# Conn4_3.net
KiCad netlist of a schematic drawn in Altium Designer
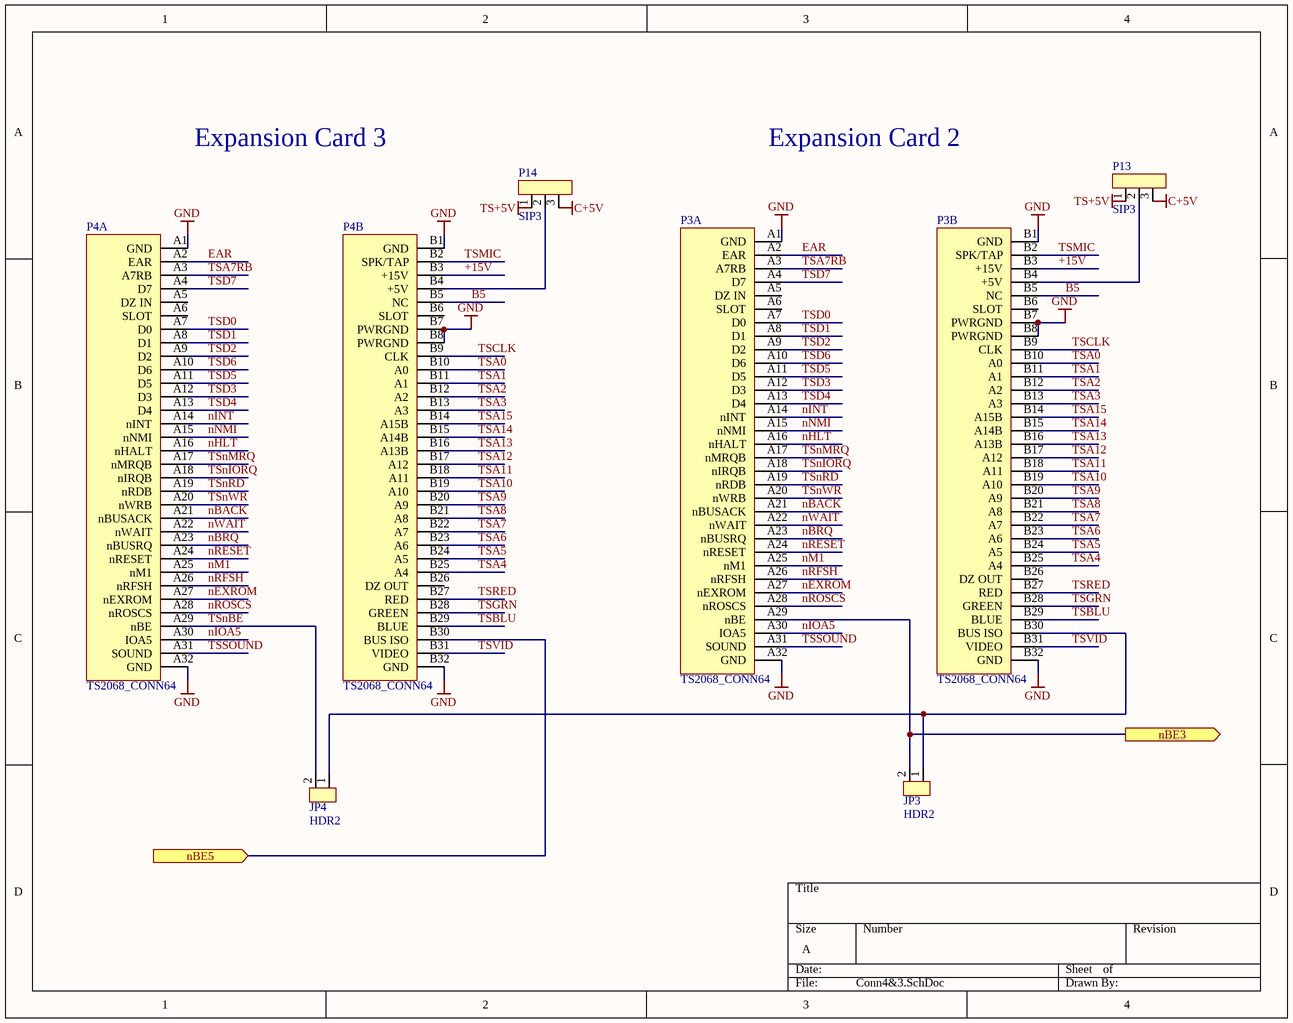
[diagram p0: Conn4&3.SchDoc]

(export (version "E")
  (design (tool "Eeschema 10.0.6"))
  (components
    (comp (ref "JP3") (value "HDR2") (footprint "HDR2") (libsource (lib "Connectors") (part "HDR2")))
    (comp (ref "JP4") (value "HDR2") (footprint "HDR2") (libsource (lib "Connectors") (part "HDR2")))
    (comp (ref "P3")
      (value "TS2068_CONN64")
      (footprint "64CARDEDGE")
      (description "64 Position Female Connector Non Specified - Dual Edge Gold 0.100\" (2.54mm) Black")
      (fields (field (name "MFG") "TD"))
      (libsource (lib "Connectors") (part "TS2068_CONN64"))
    )
    (comp (ref "P4")
      (value "TS2068_CONN64")
      (footprint "64CARDEDGE")
      (description "64 Position Female Connector Non Specified - Dual Edge Gold 0.100\" (2.54mm) Black")
      (fields (field (name "MFG") "TD"))
      (libsource (lib "Connectors") (part "TS2068_CONN64"))
    )
    (comp (ref "P13") (value "SIP3") (footprint "SIP3") (libsource (lib "Connectors") (part "SIP3")))
    (comp (ref "P14") (value "SIP3") (footprint "SIP3") (libsource (lib "Connectors") (part "SIP3")))
  )
  (nets
    (net (code "1") (name "/+15V") (class "Default")
      (node (ref "P3") (pin "B3") (pinfunction "+15V_B3") (pintype "passive"))
      (node (ref "P4") (pin "B3") (pinfunction "+15V_B3") (pintype "passive"))
    )
    (net (code "2") (name "/B5") (class "Default")
      (node (ref "P3") (pin "B5") (pinfunction "NC_B5") (pintype "passive"))
      (node (ref "P4") (pin "B5") (pinfunction "NC_B5") (pintype "passive"))
    )
    (net (code "3") (name "/EAR") (class "Default")
      (node (ref "P3") (pin "A2") (pinfunction "EAR_A2") (pintype "passive"))
      (node (ref "P4") (pin "A2") (pinfunction "EAR_A2") (pintype "passive"))
    )
    (net (code "4") (name "/TSA0") (class "Default")
      (node (ref "P3") (pin "B10") (pinfunction "A0_B10") (pintype "passive"))
      (node (ref "P4") (pin "B10") (pinfunction "A0_B10") (pintype "passive"))
    )
    (net (code "5") (name "/TSA1") (class "Default")
      (node (ref "P3") (pin "B11") (pinfunction "A1_B11") (pintype "passive"))
      (node (ref "P4") (pin "B11") (pinfunction "A1_B11") (pintype "passive"))
    )
    (net (code "6") (name "/TSA2") (class "Default")
      (node (ref "P3") (pin "B12") (pinfunction "A2_B12") (pintype "passive"))
      (node (ref "P4") (pin "B12") (pinfunction "A2_B12") (pintype "passive"))
    )
    (net (code "7") (name "/TSA3") (class "Default")
      (node (ref "P3") (pin "B13") (pinfunction "A3_B13") (pintype "passive"))
      (node (ref "P4") (pin "B13") (pinfunction "A3_B13") (pintype "passive"))
    )
    (net (code "8") (name "/TSA4") (class "Default")
      (node (ref "P3") (pin "B25") (pinfunction "A4_B25") (pintype "passive"))
      (node (ref "P4") (pin "B25") (pinfunction "A4_B25") (pintype "passive"))
    )
    (net (code "9") (name "/TSA5") (class "Default")
      (node (ref "P3") (pin "B24") (pinfunction "A5_B24") (pintype "passive"))
      (node (ref "P4") (pin "B24") (pinfunction "A5_B24") (pintype "passive"))
    )
    (net (code "10") (name "/TSA6") (class "Default")
      (node (ref "P3") (pin "B23") (pinfunction "A6_B23") (pintype "passive"))
      (node (ref "P4") (pin "B23") (pinfunction "A6_B23") (pintype "passive"))
    )
    (net (code "11") (name "/TSA7") (class "Default")
      (node (ref "P3") (pin "B22") (pinfunction "A7_B22") (pintype "passive"))
      (node (ref "P4") (pin "B22") (pinfunction "A7_B22") (pintype "passive"))
    )
    (net (code "12") (name "/TSA7RB") (class "Default")
      (node (ref "P3") (pin "A3") (pinfunction "A7RB_A3") (pintype "passive"))
      (node (ref "P4") (pin "A3") (pinfunction "A7RB_A3") (pintype "passive"))
    )
    (net (code "13") (name "/TSA8") (class "Default")
      (node (ref "P3") (pin "B21") (pinfunction "A8_B21") (pintype "passive"))
      (node (ref "P4") (pin "B21") (pinfunction "A8_B21") (pintype "passive"))
    )
    (net (code "14") (name "/TSA9") (class "Default")
      (node (ref "P3") (pin "B20") (pinfunction "A9_B20") (pintype "passive"))
      (node (ref "P4") (pin "B20") (pinfunction "A9_B20") (pintype "passive"))
    )
    (net (code "15") (name "/TSA10") (class "Default")
      (node (ref "P3") (pin "B19") (pinfunction "A10_B19") (pintype "passive"))
      (node (ref "P4") (pin "B19") (pinfunction "A10_B19") (pintype "passive"))
    )
    (net (code "16") (name "/TSA11") (class "Default")
      (node (ref "P3") (pin "B18") (pinfunction "A11_B18") (pintype "passive"))
      (node (ref "P4") (pin "B18") (pinfunction "A11_B18") (pintype "passive"))
    )
    (net (code "17") (name "/TSA12") (class "Default")
      (node (ref "P3") (pin "B17") (pinfunction "A12_B17") (pintype "passive"))
      (node (ref "P4") (pin "B17") (pinfunction "A12_B17") (pintype "passive"))
    )
    (net (code "18") (name "/TSA13") (class "Default")
      (node (ref "P3") (pin "B16") (pinfunction "A13B_B16") (pintype "passive"))
      (node (ref "P4") (pin "B16") (pinfunction "A13B_B16") (pintype "passive"))
    )
    (net (code "19") (name "/TSA14") (class "Default")
      (node (ref "P3") (pin "B15") (pinfunction "A14B_B15") (pintype "passive"))
      (node (ref "P4") (pin "B15") (pinfunction "A14B_B15") (pintype "passive"))
    )
    (net (code "20") (name "/TSA15") (class "Default")
      (node (ref "P3") (pin "B14") (pinfunction "A15B_B14") (pintype "passive"))
      (node (ref "P4") (pin "B14") (pinfunction "A15B_B14") (pintype "passive"))
    )
    (net (code "21") (name "/TSBLU") (class "Default")
      (node (ref "P3") (pin "B29") (pinfunction "BLUE_B29") (pintype "passive"))
      (node (ref "P4") (pin "B29") (pinfunction "BLUE_B29") (pintype "passive"))
    )
    (net (code "22") (name "/TSCLK") (class "Default")
      (node (ref "P3") (pin "B9") (pinfunction "CLK_B9") (pintype "passive"))
      (node (ref "P4") (pin "B9") (pinfunction "CLK_B9") (pintype "passive"))
    )
    (net (code "23") (name "/TSD0") (class "Default")
      (node (ref "P3") (pin "A7") (pinfunction "D0_A7") (pintype "passive"))
      (node (ref "P4") (pin "A7") (pinfunction "D0_A7") (pintype "passive"))
    )
    (net (code "24") (name "/TSD1") (class "Default")
      (node (ref "P3") (pin "A8") (pinfunction "D1_A8") (pintype "passive"))
      (node (ref "P4") (pin "A8") (pinfunction "D1_A8") (pintype "passive"))
    )
    (net (code "25") (name "/TSD2") (class "Default")
      (node (ref "P3") (pin "A9") (pinfunction "D2_A9") (pintype "passive"))
      (node (ref "P4") (pin "A9") (pinfunction "D2_A9") (pintype "passive"))
    )
    (net (code "26") (name "/TSD3") (class "Default")
      (node (ref "P3") (pin "A12") (pinfunction "D3_A12") (pintype "passive"))
      (node (ref "P4") (pin "A12") (pinfunction "D3_A12") (pintype "passive"))
    )
    (net (code "27") (name "/TSD4") (class "Default")
      (node (ref "P3") (pin "A13") (pinfunction "D4_A13") (pintype "passive"))
      (node (ref "P4") (pin "A13") (pinfunction "D4_A13") (pintype "passive"))
    )
    (net (code "28") (name "/TSD5") (class "Default")
      (node (ref "P3") (pin "A11") (pinfunction "D5_A11") (pintype "passive"))
      (node (ref "P4") (pin "A11") (pinfunction "D5_A11") (pintype "passive"))
    )
    (net (code "29") (name "/TSD6") (class "Default")
      (node (ref "P3") (pin "A10") (pinfunction "D6_A10") (pintype "passive"))
      (node (ref "P4") (pin "A10") (pinfunction "D6_A10") (pintype "passive"))
    )
    (net (code "30") (name "/TSD7") (class "Default")
      (node (ref "P3") (pin "A4") (pinfunction "D7_A4") (pintype "passive"))
      (node (ref "P4") (pin "A4") (pinfunction "D7_A4") (pintype "passive"))
    )
    (net (code "31") (name "/TSGRN") (class "Default")
      (node (ref "P3") (pin "B28") (pinfunction "GREEN_B28") (pintype "passive"))
      (node (ref "P4") (pin "B28") (pinfunction "GREEN_B28") (pintype "passive"))
    )
    (net (code "32") (name "/TSMIC") (class "Default")
      (node (ref "P3") (pin "B2") (pinfunction "SPK/TAP_B2") (pintype "passive"))
      (node (ref "P4") (pin "B2") (pinfunction "SPK/TAP_B2") (pintype "passive"))
    )
    (net (code "33") (name "/TSRED") (class "Default")
      (node (ref "P3") (pin "B27") (pinfunction "RED_B27") (pintype "passive"))
      (node (ref "P4") (pin "B27") (pinfunction "RED_B27") (pintype "passive"))
    )
    (net (code "34") (name "/TSSOUND") (class "Default")
      (node (ref "P3") (pin "A31") (pinfunction "SOUND_A31") (pintype "passive"))
      (node (ref "P4") (pin "A31") (pinfunction "SOUND_A31") (pintype "passive"))
    )
    (net (code "35") (name "/TSVID") (class "Default")
      (node (ref "P3") (pin "B31") (pinfunction "VIDEO_B31") (pintype "passive"))
      (node (ref "P4") (pin "B31") (pinfunction "VIDEO_B31") (pintype "passive"))
    )
    (net (code "36") (name "/TSnBE") (class "Default")
      (node (ref "JP4") (pin "2") (pintype "passive"))
      (node (ref "P4") (pin "A29") (pinfunction "nBE_A29") (pintype "passive"))
    )
    (net (code "37") (name "/TSnIORQ") (class "Default")
      (node (ref "P3") (pin "A18") (pinfunction "nIRQB_A18") (pintype "passive"))
      (node (ref "P4") (pin "A18") (pinfunction "nIRQB_A18") (pintype "passive"))
    )
    (net (code "38") (name "/TSnMRQ") (class "Default")
      (node (ref "P3") (pin "A17") (pinfunction "nMRQB_A17") (pintype "passive"))
      (node (ref "P4") (pin "A17") (pinfunction "nMRQB_A17") (pintype "passive"))
    )
    (net (code "39") (name "/TSnRD") (class "Default")
      (node (ref "P3") (pin "A19") (pinfunction "nRDB_A19") (pintype "passive"))
      (node (ref "P4") (pin "A19") (pinfunction "nRDB_A19") (pintype "passive"))
    )
    (net (code "40") (name "/TSnWR") (class "Default")
      (node (ref "P3") (pin "A20") (pinfunction "nWRB_A20") (pintype "passive"))
      (node (ref "P4") (pin "A20") (pinfunction "nWRB_A20") (pintype "passive"))
    )
    (net (code "41") (name "/nBACK") (class "Default")
      (node (ref "P3") (pin "A21") (pinfunction "nBUSACK_A21") (pintype "passive"))
      (node (ref "P4") (pin "A21") (pinfunction "nBUSACK_A21") (pintype "passive"))
    )
    (net (code "42") (name "/nBE3") (class "Default")
      (node (ref "JP3") (pin "2") (pintype "passive"))
      (node (ref "P3") (pin "A29") (pinfunction "nBE_A29") (pintype "passive"))
    )
    (net (code "43") (name "/nBE5") (class "Default")
      (node (ref "P4") (pin "B30") (pinfunction "BUS_ISO_B30") (pintype "passive"))
    )
    (net (code "44") (name "/nBRQ") (class "Default")
      (node (ref "P3") (pin "A23") (pinfunction "nBUSRQ_A23") (pintype "passive"))
      (node (ref "P4") (pin "A23") (pinfunction "nBUSRQ_A23") (pintype "passive"))
    )
    (net (code "45") (name "/nEXROM") (class "Default")
      (node (ref "P3") (pin "A27") (pinfunction "nEXROM_A27") (pintype "passive"))
      (node (ref "P4") (pin "A27") (pinfunction "nEXROM_A27") (pintype "passive"))
    )
    (net (code "46") (name "/nHLT") (class "Default")
      (node (ref "P3") (pin "A16") (pinfunction "nHALT_A16") (pintype "passive"))
      (node (ref "P4") (pin "A16") (pinfunction "nHALT_A16") (pintype "passive"))
    )
    (net (code "47") (name "/nINT") (class "Default")
      (node (ref "P3") (pin "A14") (pinfunction "nINT_A14") (pintype "passive"))
      (node (ref "P4") (pin "A14") (pinfunction "nINT_A14") (pintype "passive"))
    )
    (net (code "48") (name "/nIOA5") (class "Default")
      (node (ref "P3") (pin "A30") (pinfunction "IOA5_A30") (pintype "passive"))
      (node (ref "P4") (pin "A30") (pinfunction "IOA5_A30") (pintype "passive"))
    )
    (net (code "49") (name "/nM1") (class "Default")
      (node (ref "P3") (pin "A25") (pinfunction "nM1_A25") (pintype "passive"))
      (node (ref "P4") (pin "A25") (pinfunction "nM1_A25") (pintype "passive"))
    )
    (net (code "50") (name "/nNMI") (class "Default")
      (node (ref "P3") (pin "A15") (pinfunction "nNMI_A15") (pintype "passive"))
      (node (ref "P4") (pin "A15") (pinfunction "nNMI_A15") (pintype "passive"))
    )
    (net (code "51") (name "/nRESET") (class "Default")
      (node (ref "P3") (pin "A24") (pinfunction "nRESET_A24") (pintype "passive"))
      (node (ref "P4") (pin "A24") (pinfunction "nRESET_A24") (pintype "passive"))
    )
    (net (code "52") (name "/nRFSH") (class "Default")
      (node (ref "P3") (pin "A26") (pinfunction "nRFSH_A26") (pintype "passive"))
      (node (ref "P4") (pin "A26") (pinfunction "nRFSH_A26") (pintype "passive"))
    )
    (net (code "53") (name "/nROSCS") (class "Default")
      (node (ref "P3") (pin "A28") (pinfunction "nROSCS_A28") (pintype "passive"))
      (node (ref "P4") (pin "A28") (pinfunction "nROSCS_A28") (pintype "passive"))
    )
    (net (code "54") (name "/nWAIT") (class "Default")
      (node (ref "P3") (pin "A22") (pinfunction "nWAIT_A22") (pintype "passive"))
      (node (ref "P4") (pin "A22") (pinfunction "nWAIT_A22") (pintype "passive"))
    )
    (net (code "55") (name "C+5V") (class "Default")
      (node (ref "P13") (pin "3") (pintype "passive"))
      (node (ref "P14") (pin "3") (pintype "passive"))
    )
    (net (code "56") (name "GND") (class "Default")
      (node (ref "P3") (pin "A1") (pinfunction "GND_A1") (pintype "passive"))
      (node (ref "P3") (pin "A32") (pinfunction "GND_A32") (pintype "passive"))
      (node (ref "P3") (pin "B1") (pinfunction "GND_B1") (pintype "passive"))
      (node (ref "P3") (pin "B32") (pinfunction "GND_B32") (pintype "passive"))
      (node (ref "P3") (pin "B7") (pinfunction "PWRGND_B7") (pintype "passive"))
      (node (ref "P3") (pin "B8") (pinfunction "PWRGND_B8") (pintype "passive"))
      (node (ref "P4") (pin "A1") (pinfunction "GND_A1") (pintype "passive"))
      (node (ref "P4") (pin "A32") (pinfunction "GND_A32") (pintype "passive"))
      (node (ref "P4") (pin "B1") (pinfunction "GND_B1") (pintype "passive"))
      (node (ref "P4") (pin "B32") (pinfunction "GND_B32") (pintype "passive"))
      (node (ref "P4") (pin "B7") (pinfunction "PWRGND_B7") (pintype "passive"))
      (node (ref "P4") (pin "B8") (pinfunction "PWRGND_B8") (pintype "passive"))
    )
    (net (code "57") (name "Net-(P3B-+5V)") (class "Default")
      (node (ref "P13") (pin "2") (pintype "passive"))
      (node (ref "P3") (pin "B4") (pinfunction "+5V_B4") (pintype "passive"))
    )
    (net (code "58") (name "Net-(P3B-BUS_ISO)") (class "Default")
      (node (ref "JP3") (pin "1") (pintype "passive"))
      (node (ref "JP4") (pin "1") (pintype "passive"))
      (node (ref "P3") (pin "B30") (pinfunction "BUS_ISO_B30") (pintype "passive"))
    )
    (net (code "59") (name "Net-(P4B-+5V)") (class "Default")
      (node (ref "P14") (pin "2") (pintype "passive"))
      (node (ref "P4") (pin "B4") (pinfunction "+5V_B4") (pintype "passive"))
    )
    (net (code "60") (name "TS+5V") (class "Default")
      (node (ref "P13") (pin "1") (pintype "passive"))
      (node (ref "P14") (pin "1") (pintype "passive"))
    )
    (net (code "61") (name "unconnected-(P3A-DZ_IN-PadA5)") (class "Default")
      (node (ref "P3") (pin "A5") (pinfunction "DZ_IN_A5") (pintype "passive"))
    )
    (net (code "62") (name "unconnected-(P3A-SLOT-PadA6)") (class "Default")
      (node (ref "P3") (pin "A6") (pinfunction "SLOT_A6") (pintype "passive"))
    )
    (net (code "63") (name "unconnected-(P3B-DZ_OUT-PadB26)") (class "Default")
      (node (ref "P3") (pin "B26") (pinfunction "DZ_OUT_B26") (pintype "passive"))
    )
    (net (code "64") (name "unconnected-(P3B-SLOT-PadB6)") (class "Default")
      (node (ref "P3") (pin "B6") (pinfunction "SLOT_B6") (pintype "passive"))
    )
    (net (code "65") (name "unconnected-(P4A-DZ_IN-PadA5)") (class "Default")
      (node (ref "P4") (pin "A5") (pinfunction "DZ_IN_A5") (pintype "passive"))
    )
    (net (code "66") (name "unconnected-(P4A-SLOT-PadA6)") (class "Default")
      (node (ref "P4") (pin "A6") (pinfunction "SLOT_A6") (pintype "passive"))
    )
    (net (code "67") (name "unconnected-(P4B-DZ_OUT-PadB26)") (class "Default")
      (node (ref "P4") (pin "B26") (pinfunction "DZ_OUT_B26") (pintype "passive"))
    )
    (net (code "68") (name "unconnected-(P4B-SLOT-PadB6)") (class "Default")
      (node (ref "P4") (pin "B6") (pinfunction "SLOT_B6") (pintype "passive"))
    )
  )
)
